# Ghostbusters.net
KiCad netlist of a schematic drawn in EAGLE
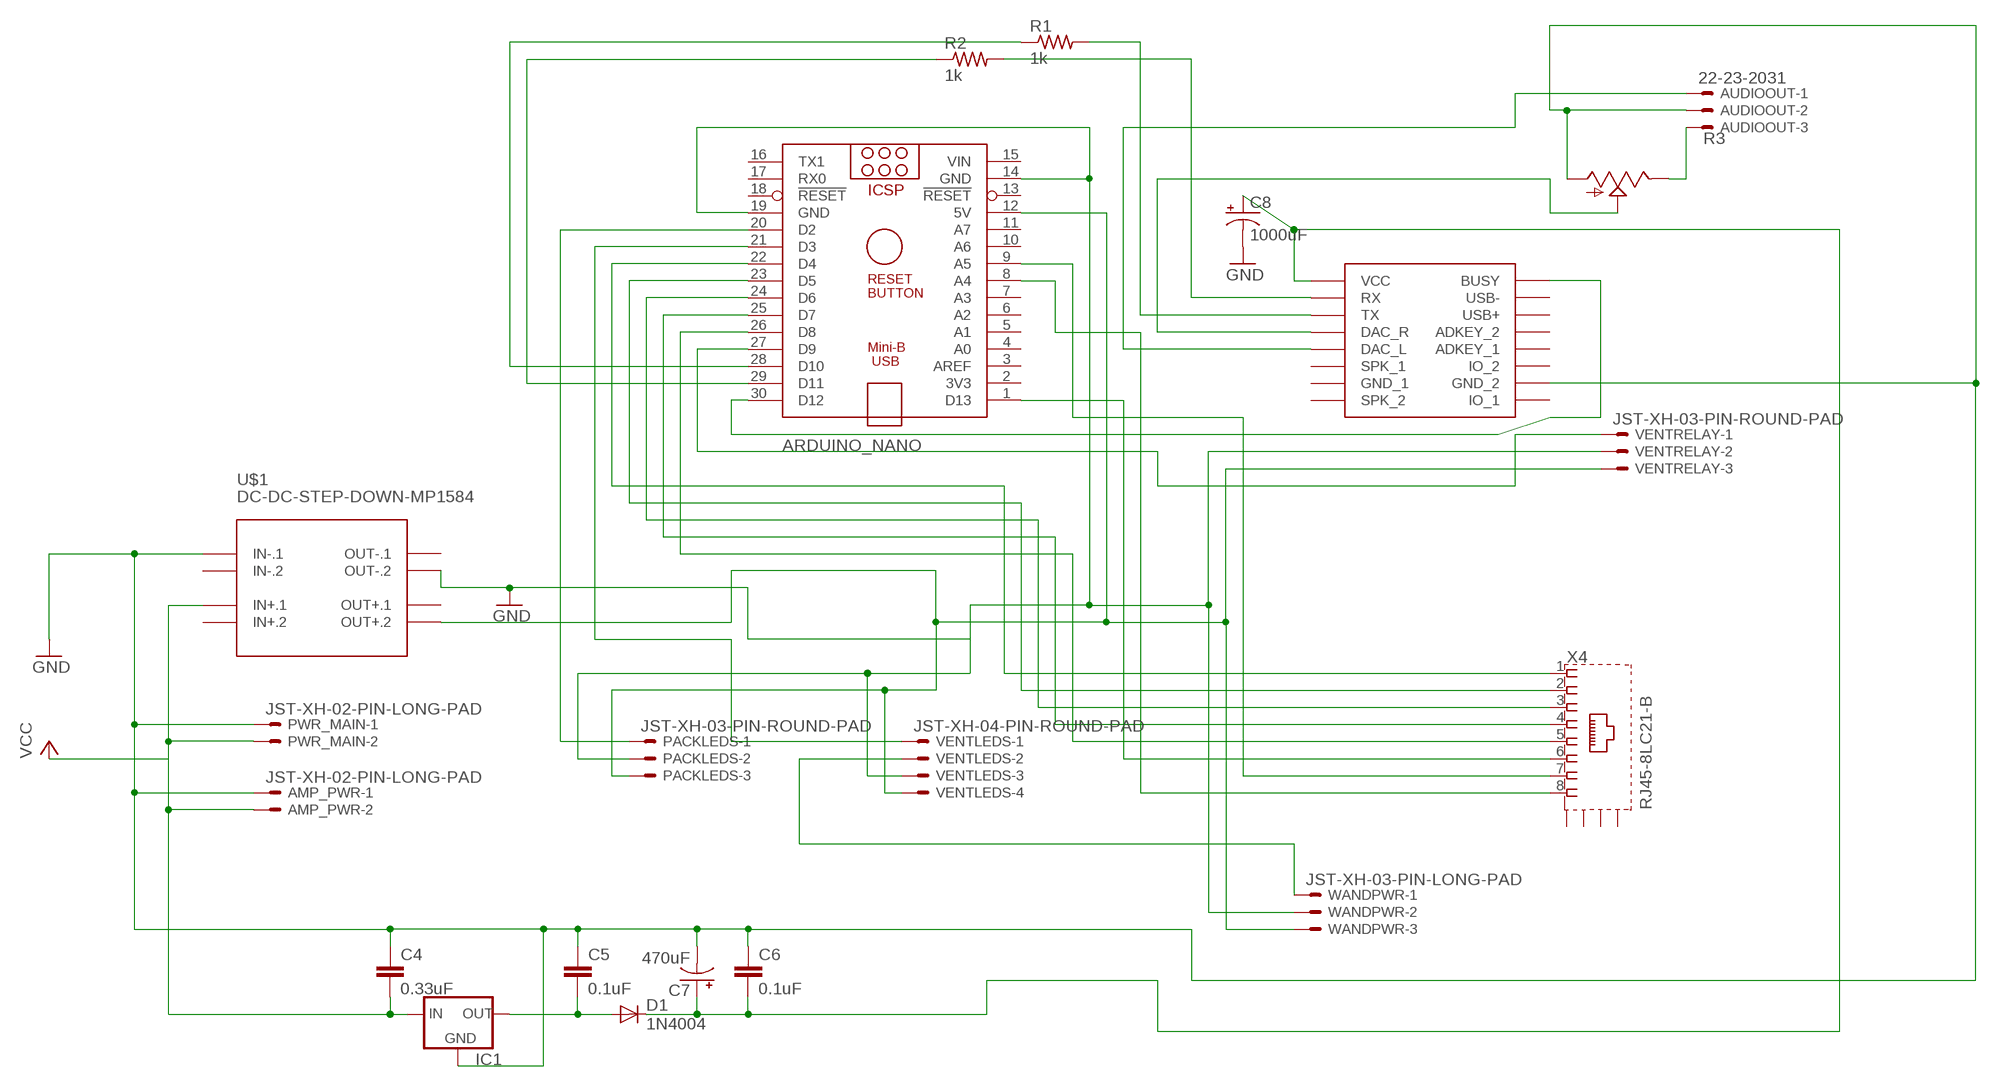
[diagram p0: schematic, sheet 1]

(export (version "E")
  (design (tool "Eeschema 10.0.6"))
  (components
    (comp (ref "AMP_PWR")
      (value "JST-XH-02-PIN-LONG-PAD")
      (footprint "eagle-import:JST-XH-02-PACKAGE-LONG-PAD")
      (libsource (lib "eagle-import") (part "JST-XH-02-PIN-LONG-PAD"))
    )
    (comp (ref "ARDUINO_NANO")
      (value "ARDUINO_NANO")
      (footprint "eagle-import:ARDUINO_NANO")
      (libsource (lib "eagle-import") (part "ARDUINO_NANO"))
    )
    (comp (ref "AUDIOOUT")
      (value "22-23-2031")
      (footprint "eagle-import:22-23-2031")
      (fields (field (name "MF") "MOLEX"))
      (libsource (lib "eagle-import") (part "22-23-2031"))
    )
    (comp (ref "C4")
      (value "0.33uF")
      (footprint "eagle-import:C2.5-4")
      (libsource (lib "eagle-import") (part "C2.5/4"))
    )
    (comp (ref "C5")
      (value "0.1uF")
      (footprint "eagle-import:C2.5-4")
      (libsource (lib "eagle-import") (part "C2.5/4"))
    )
    (comp (ref "C6")
      (value "0.1uF")
      (footprint "eagle-import:C2.5-4")
      (libsource (lib "eagle-import") (part "C2.5/4"))
    )
    (comp (ref "C7")
      (value "470uF")
      (footprint "eagle-import:TAP5-45")
      (libsource (lib "eagle-import") (part "CPOL-USTAP5-45"))
    )
    (comp (ref "C8")
      (value "1000uF")
      (footprint "eagle-import:TAP5-45")
      (libsource (lib "eagle-import") (part "CPOL-USTAP5-45"))
    )
    (comp (ref "D1")
      (value "1N4004")
      (footprint "eagle-import:DO41-10")
      (libsource (lib "eagle-import") (part "1N4004"))
    )
    (comp (ref "DFPLAYER")
      (value "DFPLAYER")
      (footprint "eagle-import:DFPLAYER")
      (libsource (lib "eagle-import") (part "DFPLAYER"))
    )
    (comp (ref "IC1")
      (value "78MXXS")
      (footprint "eagle-import:78MXXS")
      (libsource (lib "eagle-import") (part "78MXXS"))
    )
    (comp (ref "PACKLEDS")
      (value "JST-XH-03-PIN-ROUND-PAD")
      (footprint "eagle-import:JST-XH-03-PACKAGE-ROUND-PAD")
      (libsource (lib "eagle-import") (part "JST-XH-03-PIN-ROUND-PAD"))
    )
    (comp (ref "PWR_MAIN")
      (value "JST-XH-02-PIN-LONG-PAD")
      (footprint "eagle-import:JST-XH-02-PACKAGE-LONG-PAD")
      (libsource (lib "eagle-import") (part "JST-XH-02-PIN-LONG-PAD"))
    )
    (comp (ref "R1")
      (value "1k")
      (footprint "eagle-import:0207_12")
      (libsource (lib "eagle-import") (part "R-US_0207/12"))
    )
    (comp (ref "R2")
      (value "1k")
      (footprint "eagle-import:0207_12")
      (libsource (lib "eagle-import") (part "R-US_0207/12"))
    )
    (comp (ref "R3")
      (value "TRIM_US-B64Y")
      (footprint "eagle-import:B64Y")
      (libsource (lib "eagle-import") (part "TRIM_US-B64Y"))
    )
    (comp (ref "U$1")
      (value "DC-DC-STEP-DOWN-MP1584")
      (footprint "eagle-import:DC-DC-STEP-DOWN-MP1584")
      (libsource (lib "eagle-import") (part "DC-DC-STEP-DOWN-MP1584"))
    )
    (comp (ref "VENTLEDS")
      (value "JST-XH-04-PIN-ROUND-PAD")
      (footprint "eagle-import:JST-XH-04-PACKAGE-ROUND-PAD")
      (libsource (lib "eagle-import") (part "JST-XH-04-PIN-ROUND-PAD"))
    )
    (comp (ref "VENTRELAY")
      (value "JST-XH-03-PIN-ROUND-PAD")
      (footprint "eagle-import:JST-XH-03-PACKAGE-ROUND-PAD")
      (libsource (lib "eagle-import") (part "JST-XH-03-PIN-ROUND-PAD"))
    )
    (comp (ref "WANDPWR")
      (value "JST-XH-03-PIN-LONG-PAD")
      (footprint "eagle-import:JST-XH-03-PACKAGE-LONG-PAD")
      (libsource (lib "eagle-import") (part "JST-XH-03-PIN-LONG-PAD"))
    )
    (comp (ref "X4")
      (value "RJ45-8LC21-B")
      (footprint "eagle-import:RJ45-SHIELD1")
      (libsource (lib "eagle-import") (part "RJ4521-B-8LC"))
    )
  )
  (nets
    (net (code "1") (name "/VIN") (class "Default")
      (node (ref "ARDUINO_NANO") (pin "15") (pinfunction "VIN_15") (pintype "power_in"))
    )
    (net (code "2") (name "GND") (class "Default")
      (node (ref "AMP_PWR") (pin "1") (pinfunction "S_1") (pintype "passive"))
      (node (ref "ARDUINO_NANO") (pin "14") (pinfunction "GND_14") (pintype "power_in"))
      (node (ref "ARDUINO_NANO") (pin "19") (pinfunction "GND_19") (pintype "power_in"))
      (node (ref "AUDIOOUT") (pin "2") (pinfunction "S_2") (pintype "passive"))
      (node (ref "C4") (pin "1") (pinfunction "1_1") (pintype "passive"))
      (node (ref "C5") (pin "1") (pinfunction "1_1") (pintype "passive"))
      (node (ref "C6") (pin "1") (pinfunction "1_1") (pintype "passive"))
      (node (ref "C7") (pin "-") (pinfunction "-_-") (pintype "passive"))
      (node (ref "C8") (pin "-") (pinfunction "-_-") (pintype "passive"))
      (node (ref "DFPLAYER") (pin "GND_2") (pinfunction "GND_2_GND_2") (pintype "bidirectional"))
      (node (ref "IC1") (pin "GND") (pinfunction "GND_GND") (pintype "input"))
      (node (ref "PACKLEDS") (pin "2") (pinfunction "S_2") (pintype "passive"))
      (node (ref "PWR_MAIN") (pin "1") (pinfunction "S_1") (pintype "passive"))
      (node (ref "R3") (pin "A") (pinfunction "A_A") (pintype "passive"))
      (node (ref "U$1") (pin "IN-.1") (pinfunction "IN-.1_IN-.1") (pintype "bidirectional"))
      (node (ref "U$1") (pin "OUT-.2") (pinfunction "OUT-.2_OUT-.2") (pintype "bidirectional"))
      (node (ref "VENTLEDS") (pin "3") (pinfunction "S_3") (pintype "passive"))
      (node (ref "VENTRELAY") (pin "2") (pinfunction "S_2") (pintype "passive"))
      (node (ref "WANDPWR") (pin "2") (pinfunction "S_2") (pintype "passive"))
    )
    (net (code "3") (name "Net-(ARDUINO_NANO-5V)") (class "Default")
      (node (ref "ARDUINO_NANO") (pin "12") (pinfunction "5V_12") (pintype "power_in"))
      (node (ref "PACKLEDS") (pin "3") (pinfunction "S_3") (pintype "passive"))
      (node (ref "U$1") (pin "OUT+.2") (pinfunction "OUT+.2_OUT+.2") (pintype "bidirectional"))
      (node (ref "VENTLEDS") (pin "4") (pinfunction "S_4") (pintype "passive"))
      (node (ref "VENTRELAY") (pin "3") (pinfunction "S_3") (pintype "passive"))
      (node (ref "WANDPWR") (pin "3") (pinfunction "S_3") (pintype "passive"))
    )
    (net (code "4") (name "Net-(ARDUINO_NANO-A4)") (class "Default")
      (node (ref "ARDUINO_NANO") (pin "8") (pinfunction "A4_8") (pintype "bidirectional"))
      (node (ref "X4") (pin "8") (pinfunction "8_8") (pintype "passive"))
    )
    (net (code "5") (name "Net-(ARDUINO_NANO-A5)") (class "Default")
      (node (ref "ARDUINO_NANO") (pin "9") (pinfunction "A5_9") (pintype "bidirectional"))
      (node (ref "X4") (pin "7") (pinfunction "7_7") (pintype "passive"))
    )
    (net (code "6") (name "Net-(ARDUINO_NANO-D2)") (class "Default")
      (node (ref "ARDUINO_NANO") (pin "20") (pinfunction "D2_20") (pintype "bidirectional"))
      (node (ref "PACKLEDS") (pin "1") (pinfunction "S_1") (pintype "passive"))
    )
    (net (code "7") (name "Net-(ARDUINO_NANO-D3)") (class "Default")
      (node (ref "ARDUINO_NANO") (pin "21") (pinfunction "D3_21") (pintype "bidirectional"))
      (node (ref "VENTLEDS") (pin "1") (pinfunction "S_1") (pintype "passive"))
    )
    (net (code "8") (name "Net-(ARDUINO_NANO-D4)") (class "Default")
      (node (ref "ARDUINO_NANO") (pin "22") (pinfunction "D4_22") (pintype "bidirectional"))
      (node (ref "X4") (pin "1") (pinfunction "1_1") (pintype "passive"))
    )
    (net (code "9") (name "Net-(ARDUINO_NANO-D5)") (class "Default")
      (node (ref "ARDUINO_NANO") (pin "23") (pinfunction "D5_23") (pintype "bidirectional"))
      (node (ref "X4") (pin "2") (pinfunction "2_2") (pintype "passive"))
    )
    (net (code "10") (name "Net-(ARDUINO_NANO-D6)") (class "Default")
      (node (ref "ARDUINO_NANO") (pin "24") (pinfunction "D6_24") (pintype "bidirectional"))
      (node (ref "X4") (pin "3") (pinfunction "3_3") (pintype "passive"))
    )
    (net (code "11") (name "Net-(ARDUINO_NANO-D7)") (class "Default")
      (node (ref "ARDUINO_NANO") (pin "25") (pinfunction "D7_25") (pintype "bidirectional"))
      (node (ref "X4") (pin "4") (pinfunction "4_4") (pintype "passive"))
    )
    (net (code "12") (name "Net-(ARDUINO_NANO-D8)") (class "Default")
      (node (ref "ARDUINO_NANO") (pin "26") (pinfunction "D8_26") (pintype "bidirectional"))
      (node (ref "X4") (pin "5") (pinfunction "5_5") (pintype "passive"))
    )
    (net (code "13") (name "Net-(ARDUINO_NANO-D9)") (class "Default")
      (node (ref "ARDUINO_NANO") (pin "27") (pinfunction "D9_27") (pintype "bidirectional"))
      (node (ref "VENTRELAY") (pin "1") (pinfunction "S_1") (pintype "passive"))
    )
    (net (code "14") (name "Net-(ARDUINO_NANO-D10)") (class "Default")
      (node (ref "ARDUINO_NANO") (pin "28") (pinfunction "D10_28") (pintype "bidirectional"))
      (node (ref "R1") (pin "1") (pinfunction "1_1") (pintype "passive"))
    )
    (net (code "15") (name "Net-(ARDUINO_NANO-D11)") (class "Default")
      (node (ref "ARDUINO_NANO") (pin "29") (pinfunction "D11_29") (pintype "bidirectional"))
      (node (ref "R2") (pin "1") (pinfunction "1_1") (pintype "passive"))
    )
    (net (code "16") (name "Net-(ARDUINO_NANO-D12)") (class "Default")
      (node (ref "ARDUINO_NANO") (pin "30") (pinfunction "D12_30") (pintype "bidirectional"))
      (node (ref "DFPLAYER") (pin "BUSY") (pinfunction "BUSY_BUSY") (pintype "bidirectional"))
    )
    (net (code "17") (name "Net-(ARDUINO_NANO-D13)") (class "Default")
      (node (ref "ARDUINO_NANO") (pin "1") (pinfunction "D13_1") (pintype "bidirectional"))
      (node (ref "X4") (pin "6") (pinfunction "6_6") (pintype "passive"))
    )
    (net (code "18") (name "Net-(AUDIOOUTA-S)") (class "Default")
      (node (ref "AUDIOOUT") (pin "1") (pinfunction "S_1") (pintype "passive"))
      (node (ref "DFPLAYER") (pin "DAC_L") (pinfunction "DAC_L_DAC_L") (pintype "bidirectional"))
    )
    (net (code "19") (name "Net-(AUDIOOUTC-S)") (class "Default")
      (node (ref "AUDIOOUT") (pin "3") (pinfunction "S_3") (pintype "passive"))
      (node (ref "R3") (pin "E") (pinfunction "E_E") (pintype "passive"))
    )
    (net (code "20") (name "Net-(C5-Pad2)") (class "Default")
      (node (ref "C5") (pin "2") (pinfunction "2_2") (pintype "passive"))
      (node (ref "D1") (pin "A") (pinfunction "A_A") (pintype "passive"))
      (node (ref "IC1") (pin "OUT") (pinfunction "OUT_OUT") (pintype "passive"))
    )
    (net (code "21") (name "Net-(C6-Pad2)") (class "Default")
      (node (ref "C6") (pin "2") (pinfunction "2_2") (pintype "passive"))
      (node (ref "C7") (pin "+") (pinfunction "+_+") (pintype "passive"))
      (node (ref "C8") (pin "+") (pinfunction "+_+") (pintype "passive"))
      (node (ref "D1") (pin "C") (pinfunction "C_C") (pintype "passive"))
      (node (ref "DFPLAYER") (pin "VCC") (pinfunction "VCC_VCC") (pintype "bidirectional"))
    )
    (net (code "22") (name "Net-(DFPLAYER-PadDAC_R)") (class "Default")
      (node (ref "DFPLAYER") (pin "DAC_R") (pinfunction "DAC_R_DAC_R") (pintype "bidirectional"))
      (node (ref "R3") (pin "S") (pinfunction "S_S") (pintype "passive"))
    )
    (net (code "23") (name "Net-(DFPLAYER-PadRX)") (class "Default")
      (node (ref "DFPLAYER") (pin "RX") (pinfunction "RX_RX") (pintype "bidirectional"))
      (node (ref "R2") (pin "2") (pinfunction "2_2") (pintype "passive"))
    )
    (net (code "24") (name "Net-(DFPLAYER-PadTX)") (class "Default")
      (node (ref "DFPLAYER") (pin "TX") (pinfunction "TX_TX") (pintype "bidirectional"))
      (node (ref "R1") (pin "2") (pinfunction "2_2") (pintype "passive"))
    )
    (net (code "25") (name "Net-(VENTLEDSB-S)") (class "Default")
      (node (ref "VENTLEDS") (pin "2") (pinfunction "S_2") (pintype "passive"))
      (node (ref "WANDPWR") (pin "1") (pinfunction "S_1") (pintype "passive"))
    )
    (net (code "26") (name "VCC") (class "Default")
      (node (ref "AMP_PWR") (pin "2") (pinfunction "S_2") (pintype "passive"))
      (node (ref "C4") (pin "2") (pinfunction "2_2") (pintype "passive"))
      (node (ref "IC1") (pin "IN") (pinfunction "IN_IN") (pintype "input"))
      (node (ref "PWR_MAIN") (pin "2") (pinfunction "S_2") (pintype "passive"))
      (node (ref "U$1") (pin "IN+.1") (pinfunction "IN+.1_IN+.1") (pintype "bidirectional"))
    )
    (net (code "27") (name "unconnected-(ARDUINO_NANO-3V3-Pad2)") (class "Default")
      (node (ref "ARDUINO_NANO") (pin "2") (pinfunction "3V3_2") (pintype "output"))
    )
    (net (code "28") (name "unconnected-(ARDUINO_NANO-A0-Pad4)") (class "Default")
      (node (ref "ARDUINO_NANO") (pin "4") (pinfunction "A0_4") (pintype "bidirectional"))
    )
    (net (code "29") (name "unconnected-(ARDUINO_NANO-A1-Pad5)") (class "Default")
      (node (ref "ARDUINO_NANO") (pin "5") (pinfunction "A1_5") (pintype "bidirectional"))
    )
    (net (code "30") (name "unconnected-(ARDUINO_NANO-A2-Pad6)") (class "Default")
      (node (ref "ARDUINO_NANO") (pin "6") (pinfunction "A2_6") (pintype "bidirectional"))
    )
    (net (code "31") (name "unconnected-(ARDUINO_NANO-A3-Pad7)") (class "Default")
      (node (ref "ARDUINO_NANO") (pin "7") (pinfunction "A3_7") (pintype "bidirectional"))
    )
    (net (code "32") (name "unconnected-(ARDUINO_NANO-A6-Pad10)") (class "Default")
      (node (ref "ARDUINO_NANO") (pin "10") (pinfunction "A6_10") (pintype "bidirectional"))
    )
    (net (code "33") (name "unconnected-(ARDUINO_NANO-A7-Pad11)") (class "Default")
      (node (ref "ARDUINO_NANO") (pin "11") (pinfunction "A7_11") (pintype "bidirectional"))
    )
    (net (code "34") (name "unconnected-(ARDUINO_NANO-AREF-Pad3)") (class "Default")
      (node (ref "ARDUINO_NANO") (pin "3") (pinfunction "AREF_3") (pintype "input"))
    )
    (net (code "35") (name "unconnected-(ARDUINO_NANO-RX0-Pad17)") (class "Default")
      (node (ref "ARDUINO_NANO") (pin "17") (pinfunction "RX0_17") (pintype "bidirectional"))
    )
    (net (code "36") (name "unconnected-(ARDUINO_NANO-TX1-Pad16)") (class "Default")
      (node (ref "ARDUINO_NANO") (pin "16") (pinfunction "TX1_16") (pintype "bidirectional"))
    )
    (net (code "37") (name "unconnected-(ARDUINO_NANO-~{RESET}-Pad13)") (class "Default")
      (node (ref "ARDUINO_NANO") (pin "13") (pinfunction "~{RESET}_13") (pintype "input"))
    )
    (net (code "38") (name "unconnected-(ARDUINO_NANO-~{RESET}-Pad18)") (class "Default")
      (node (ref "ARDUINO_NANO") (pin "18") (pinfunction "~{RESET}_18") (pintype "input"))
    )
    (net (code "39") (name "unconnected-(DFPLAYER-ADKEY_1-PadADKEY1)") (class "Default")
      (node (ref "DFPLAYER") (pin "ADKEY1") (pinfunction "ADKEY_1_ADKEY1") (pintype "bidirectional"))
    )
    (net (code "40") (name "unconnected-(DFPLAYER-ADKEY_2-PadADKEY2)") (class "Default")
      (node (ref "DFPLAYER") (pin "ADKEY2") (pinfunction "ADKEY_2_ADKEY2") (pintype "bidirectional"))
    )
    (net (code "41") (name "unconnected-(DFPLAYER-IO_1-PadIO1)") (class "Default")
      (node (ref "DFPLAYER") (pin "IO1") (pinfunction "IO_1_IO1") (pintype "bidirectional"))
    )
    (net (code "42") (name "unconnected-(DFPLAYER-IO_2-PadIO2)") (class "Default")
      (node (ref "DFPLAYER") (pin "IO2") (pinfunction "IO_2_IO2") (pintype "bidirectional"))
    )
    (net (code "43") (name "unconnected-(DFPLAYER-PadGND_1)") (class "Default")
      (node (ref "DFPLAYER") (pin "GND_1") (pinfunction "GND_1_GND_1") (pintype "bidirectional"))
    )
    (net (code "44") (name "unconnected-(DFPLAYER-PadUSB+)") (class "Default")
      (node (ref "DFPLAYER") (pin "USB+") (pinfunction "USB+_USB+") (pintype "bidirectional"))
    )
    (net (code "45") (name "unconnected-(DFPLAYER-PadUSB-)") (class "Default")
      (node (ref "DFPLAYER") (pin "USB-") (pinfunction "USB-_USB-") (pintype "bidirectional"))
    )
    (net (code "46") (name "unconnected-(DFPLAYER-SPK_1-PadSPK1)") (class "Default")
      (node (ref "DFPLAYER") (pin "SPK1") (pinfunction "SPK_1_SPK1") (pintype "bidirectional"))
    )
    (net (code "47") (name "unconnected-(DFPLAYER-SPK_2-PadSPK2)") (class "Default")
      (node (ref "DFPLAYER") (pin "SPK2") (pinfunction "SPK_2_SPK2") (pintype "bidirectional"))
    )
    (net (code "48") (name "unconnected-(U$1-PadIN+.2)") (class "Default")
      (node (ref "U$1") (pin "IN+.2") (pinfunction "IN+.2_IN+.2") (pintype "bidirectional"))
    )
    (net (code "49") (name "unconnected-(U$1-PadIN-.2)") (class "Default")
      (node (ref "U$1") (pin "IN-.2") (pinfunction "IN-.2_IN-.2") (pintype "bidirectional"))
    )
    (net (code "50") (name "unconnected-(U$1-PadOUT+.1)") (class "Default")
      (node (ref "U$1") (pin "OUT+.1") (pinfunction "OUT+.1_OUT+.1") (pintype "bidirectional"))
    )
    (net (code "51") (name "unconnected-(U$1-PadOUT-.1)") (class "Default")
      (node (ref "U$1") (pin "OUT-.1") (pinfunction "OUT-.1_OUT-.1") (pintype "bidirectional"))
    )
    (net (code "52") (name "unconnected-(X4-S-PadS1)") (class "Default")
      (node (ref "X4") (pin "S1") (pinfunction "S_S1") (pintype "passive"))
    )
    (net (code "53") (name "unconnected-(X4-S-PadS2)") (class "Default")
      (node (ref "X4") (pin "S2") (pinfunction "S_S2") (pintype "passive"))
    )
    (net (code "54") (name "unconnected-(X4-S-PadS3)") (class "Default")
      (node (ref "X4") (pin "S3") (pinfunction "S_S3") (pintype "passive"))
    )
    (net (code "55") (name "unconnected-(X4-S-PadS4)") (class "Default")
      (node (ref "X4") (pin "S4") (pinfunction "S_S4") (pintype "passive"))
    )
  )
)
